# MotorShield.net
KiCad netlist of a schematic drawn in EAGLE
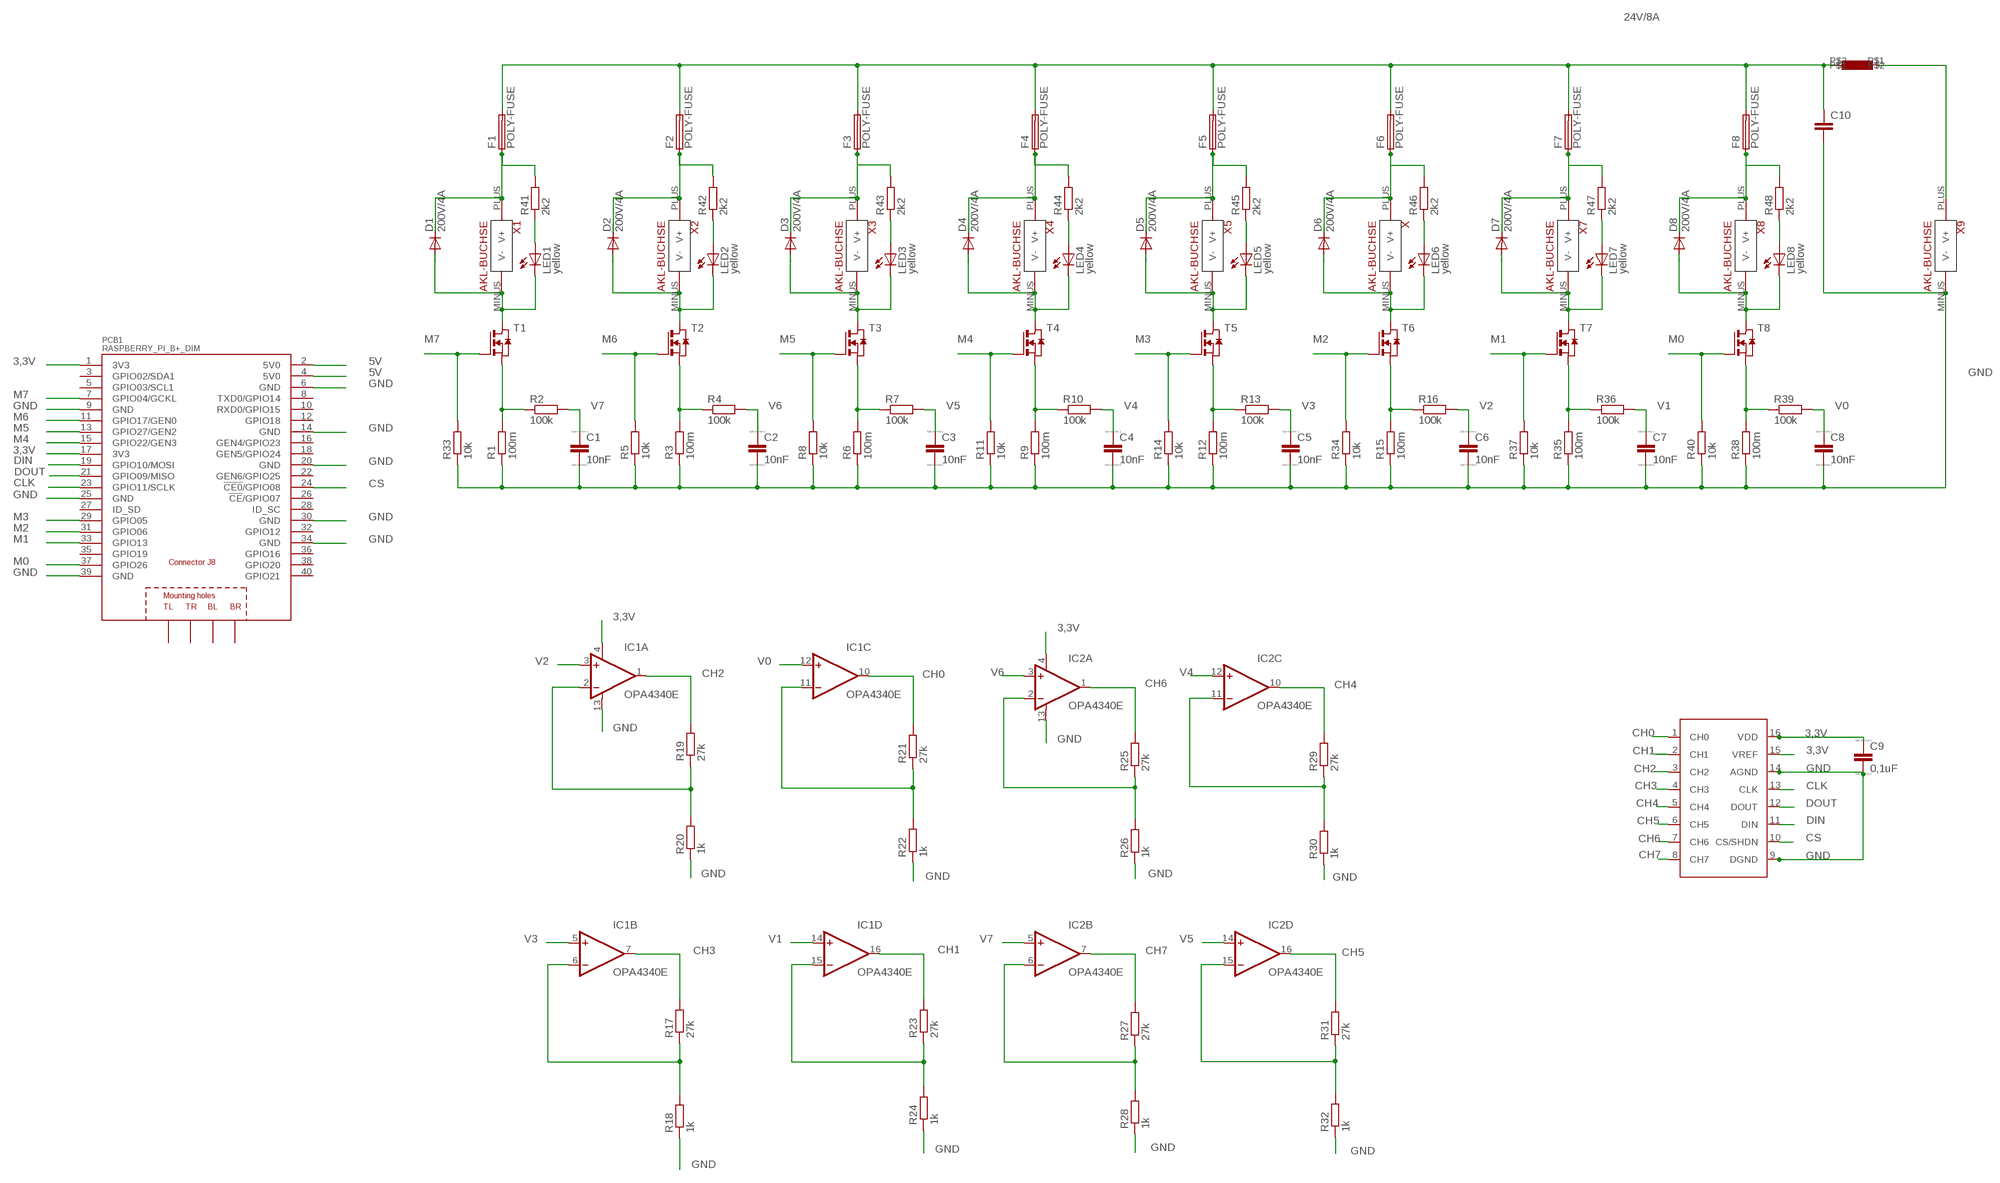
[diagram p0: schematic, sheet 1]

(export (version "E")
  (design (tool "Eeschema 10.0.6"))
  (components
    (comp (ref "C1")
      (value "10nF")
      (footprint "eagle-import:C0805")
      (libsource (lib "eagle-import") (part "C"))
    )
    (comp (ref "C2")
      (value "10nF")
      (footprint "eagle-import:C0805")
      (libsource (lib "eagle-import") (part "C"))
    )
    (comp (ref "C3")
      (value "10nF")
      (footprint "eagle-import:C0805")
      (libsource (lib "eagle-import") (part "C"))
    )
    (comp (ref "C4")
      (value "10nF")
      (footprint "eagle-import:C0805")
      (libsource (lib "eagle-import") (part "C"))
    )
    (comp (ref "C5")
      (value "10nF")
      (footprint "eagle-import:C0805")
      (libsource (lib "eagle-import") (part "C"))
    )
    (comp (ref "C6")
      (value "10nF")
      (footprint "eagle-import:C0805")
      (libsource (lib "eagle-import") (part "C"))
    )
    (comp (ref "C7")
      (value "10nF")
      (footprint "eagle-import:C0805")
      (libsource (lib "eagle-import") (part "C"))
    )
    (comp (ref "C8")
      (value "10nF")
      (footprint "eagle-import:C0805")
      (libsource (lib "eagle-import") (part "C"))
    )
    (comp (ref "C9")
      (value "0,1uF")
      (footprint "eagle-import:C0805")
      (libsource (lib "eagle-import") (part "C"))
    )
    (comp (ref "C10")
      (value "C-EUC1812")
      (footprint "eagle-import:C1812")
      (libsource (lib "eagle-import") (part "C-EUC1812"))
    )
    (comp (ref "D1")
      (value "200V/4A")
      (footprint "eagle-import:DO214AA")
      (libsource (lib "eagle-import") (part "DIODE-DO214AA"))
    )
    (comp (ref "D2")
      (value "200V/4A")
      (footprint "eagle-import:DO214AA")
      (libsource (lib "eagle-import") (part "DIODE-DO214AA"))
    )
    (comp (ref "D3")
      (value "200V/4A")
      (footprint "eagle-import:DO214AA")
      (libsource (lib "eagle-import") (part "DIODE-DO214AA"))
    )
    (comp (ref "D4")
      (value "200V/4A")
      (footprint "eagle-import:DO214AA")
      (libsource (lib "eagle-import") (part "DIODE-DO214AA"))
    )
    (comp (ref "D5")
      (value "200V/4A")
      (footprint "eagle-import:DO214AA")
      (libsource (lib "eagle-import") (part "DIODE-DO214AA"))
    )
    (comp (ref "D6")
      (value "200V/4A")
      (footprint "eagle-import:DO214AA")
      (libsource (lib "eagle-import") (part "DIODE-DO214AA"))
    )
    (comp (ref "D7")
      (value "200V/4A")
      (footprint "eagle-import:DO214AA")
      (libsource (lib "eagle-import") (part "DIODE-DO214AA"))
    )
    (comp (ref "D8")
      (value "200V/4A")
      (footprint "eagle-import:DO214AA")
      (libsource (lib "eagle-import") (part "DIODE-DO214AA"))
    )
    (comp (ref "F1")
      (value "POLY-FUSE")
      (footprint "eagle-import:1812L050")
      (libsource (lib "eagle-import") (part "POLY-FUSE"))
    )
    (comp (ref "F2")
      (value "POLY-FUSE")
      (footprint "eagle-import:1812L050")
      (libsource (lib "eagle-import") (part "POLY-FUSE"))
    )
    (comp (ref "F3")
      (value "POLY-FUSE")
      (footprint "eagle-import:1812L050")
      (libsource (lib "eagle-import") (part "POLY-FUSE"))
    )
    (comp (ref "F4")
      (value "POLY-FUSE")
      (footprint "eagle-import:1812L050")
      (libsource (lib "eagle-import") (part "POLY-FUSE"))
    )
    (comp (ref "F5")
      (value "POLY-FUSE")
      (footprint "eagle-import:1812L050")
      (libsource (lib "eagle-import") (part "POLY-FUSE"))
    )
    (comp (ref "F6")
      (value "POLY-FUSE")
      (footprint "eagle-import:1812L050")
      (libsource (lib "eagle-import") (part "POLY-FUSE"))
    )
    (comp (ref "F7")
      (value "POLY-FUSE")
      (footprint "eagle-import:1812L050")
      (libsource (lib "eagle-import") (part "POLY-FUSE"))
    )
    (comp (ref "F8")
      (value "POLY-FUSE")
      (footprint "eagle-import:1812L050")
      (libsource (lib "eagle-import") (part "POLY-FUSE"))
    )
    (comp (ref "IC1")
      (value "OPA4340E")
      (footprint "eagle-import:SSOP16BU")
      (fields (field (name "MPN") "OPA4340EA/250G4"))
      (libsource (lib "eagle-import") (part "OPA4340E"))
    )
    (comp (ref "IC2")
      (value "OPA4340E")
      (footprint "eagle-import:SSOP16BU")
      (fields (field (name "MPN") "OPA4340EA/250G4"))
      (libsource (lib "eagle-import") (part "OPA4340E"))
    )
    (comp (ref "IC3")
      (value "MCP3008SO16")
      (footprint "eagle-import:SO16")
      (libsource (lib "eagle-import") (part "MCP3008SO16"))
    )
    (comp (ref "L1")
      (value "MPI4040")
      (footprint "eagle-import:4040")
      (libsource (lib "eagle-import") (part "MPI4040"))
    )
    (comp (ref "LED1")
      (value "yellow")
      (footprint "eagle-import:CHIP-LED0603")
      (libsource (lib "eagle-import") (part "LEDCHIP-LED0603"))
    )
    (comp (ref "LED2")
      (value "yellow")
      (footprint "eagle-import:CHIP-LED0603")
      (libsource (lib "eagle-import") (part "LEDCHIP-LED0603"))
    )
    (comp (ref "LED3")
      (value "yellow")
      (footprint "eagle-import:CHIP-LED0603")
      (libsource (lib "eagle-import") (part "LEDCHIP-LED0603"))
    )
    (comp (ref "LED4")
      (value "yellow")
      (footprint "eagle-import:CHIP-LED0603")
      (libsource (lib "eagle-import") (part "LEDCHIP-LED0603"))
    )
    (comp (ref "LED5")
      (value "yellow")
      (footprint "eagle-import:CHIP-LED0603")
      (libsource (lib "eagle-import") (part "LEDCHIP-LED0603"))
    )
    (comp (ref "LED6")
      (value "yellow")
      (footprint "eagle-import:CHIP-LED0603")
      (libsource (lib "eagle-import") (part "LEDCHIP-LED0603"))
    )
    (comp (ref "LED7")
      (value "yellow")
      (footprint "eagle-import:CHIP-LED0603")
      (libsource (lib "eagle-import") (part "LEDCHIP-LED0603"))
    )
    (comp (ref "LED8")
      (value "yellow")
      (footprint "eagle-import:CHIP-LED0603")
      (libsource (lib "eagle-import") (part "LEDCHIP-LED0603"))
    )
    (comp (ref "PCB1")
      (value "RASPBERRY_PI_B+_DIM")
      (footprint "eagle-import:RASPBERRY_PI_BPLUS_DIM")
      (libsource (lib "eagle-import") (part "RASPBERRY_PI_B+_DIM"))
    )
    (comp (ref "R1")
      (value "100m")
      (footprint "eagle-import:R0805")
      (libsource (lib "eagle-import") (part "R-EU_R0805"))
    )
    (comp (ref "R2")
      (value "100k")
      (footprint "eagle-import:R0805")
      (libsource (lib "eagle-import") (part "R-EU_R0805"))
    )
    (comp (ref "R3")
      (value "100m")
      (footprint "eagle-import:R0805")
      (libsource (lib "eagle-import") (part "R-EU_R0805"))
    )
    (comp (ref "R4")
      (value "100k")
      (footprint "eagle-import:R0805")
      (libsource (lib "eagle-import") (part "R-EU_R0805"))
    )
    (comp (ref "R5")
      (value "10k")
      (footprint "eagle-import:R0805")
      (libsource (lib "eagle-import") (part "R-EU_R0805"))
    )
    (comp (ref "R6")
      (value "100m")
      (footprint "eagle-import:R0805")
      (libsource (lib "eagle-import") (part "R-EU_R0805"))
    )
    (comp (ref "R7")
      (value "100k")
      (footprint "eagle-import:R0805")
      (libsource (lib "eagle-import") (part "R-EU_R0805"))
    )
    (comp (ref "R8")
      (value "10k")
      (footprint "eagle-import:R0805")
      (libsource (lib "eagle-import") (part "R-EU_R0805"))
    )
    (comp (ref "R9")
      (value "100m")
      (footprint "eagle-import:R0805")
      (libsource (lib "eagle-import") (part "R-EU_R0805"))
    )
    (comp (ref "R10")
      (value "100k")
      (footprint "eagle-import:R0805")
      (libsource (lib "eagle-import") (part "R-EU_R0805"))
    )
    (comp (ref "R11")
      (value "10k")
      (footprint "eagle-import:R0805")
      (libsource (lib "eagle-import") (part "R-EU_R0805"))
    )
    (comp (ref "R12")
      (value "100m")
      (footprint "eagle-import:R0805")
      (libsource (lib "eagle-import") (part "R-EU_R0805"))
    )
    (comp (ref "R13")
      (value "100k")
      (footprint "eagle-import:R0805")
      (libsource (lib "eagle-import") (part "R-EU_R0805"))
    )
    (comp (ref "R14")
      (value "10k")
      (footprint "eagle-import:R0805")
      (libsource (lib "eagle-import") (part "R-EU_R0805"))
    )
    (comp (ref "R15")
      (value "100m")
      (footprint "eagle-import:R0805")
      (libsource (lib "eagle-import") (part "R-EU_R0805"))
    )
    (comp (ref "R16")
      (value "100k")
      (footprint "eagle-import:R0805")
      (libsource (lib "eagle-import") (part "R-EU_R0805"))
    )
    (comp (ref "R17")
      (value "27k")
      (footprint "eagle-import:R0805")
      (libsource (lib "eagle-import") (part "R-EU_R0805"))
    )
    (comp (ref "R18")
      (value "1k")
      (footprint "eagle-import:R0805")
      (libsource (lib "eagle-import") (part "R-EU_R0805"))
    )
    (comp (ref "R19")
      (value "27k")
      (footprint "eagle-import:R0805")
      (libsource (lib "eagle-import") (part "R-EU_R0805"))
    )
    (comp (ref "R20")
      (value "1k")
      (footprint "eagle-import:R0805")
      (libsource (lib "eagle-import") (part "R-EU_R0805"))
    )
    (comp (ref "R21")
      (value "27k")
      (footprint "eagle-import:R0805")
      (libsource (lib "eagle-import") (part "R-EU_R0805"))
    )
    (comp (ref "R22")
      (value "1k")
      (footprint "eagle-import:R0805")
      (libsource (lib "eagle-import") (part "R-EU_R0805"))
    )
    (comp (ref "R23")
      (value "27k")
      (footprint "eagle-import:R0805")
      (libsource (lib "eagle-import") (part "R-EU_R0805"))
    )
    (comp (ref "R24")
      (value "1k")
      (footprint "eagle-import:R0805")
      (libsource (lib "eagle-import") (part "R-EU_R0805"))
    )
    (comp (ref "R25")
      (value "27k")
      (footprint "eagle-import:R0805")
      (libsource (lib "eagle-import") (part "R-EU_R0805"))
    )
    (comp (ref "R26")
      (value "1k")
      (footprint "eagle-import:R0805")
      (libsource (lib "eagle-import") (part "R-EU_R0805"))
    )
    (comp (ref "R27")
      (value "27k")
      (footprint "eagle-import:R0805")
      (libsource (lib "eagle-import") (part "R-EU_R0805"))
    )
    (comp (ref "R28")
      (value "1k")
      (footprint "eagle-import:R0805")
      (libsource (lib "eagle-import") (part "R-EU_R0805"))
    )
    (comp (ref "R29")
      (value "27k")
      (footprint "eagle-import:R0805")
      (libsource (lib "eagle-import") (part "R-EU_R0805"))
    )
    (comp (ref "R30")
      (value "1k")
      (footprint "eagle-import:R0805")
      (libsource (lib "eagle-import") (part "R-EU_R0805"))
    )
    (comp (ref "R31")
      (value "27k")
      (footprint "eagle-import:R0805")
      (libsource (lib "eagle-import") (part "R-EU_R0805"))
    )
    (comp (ref "R32")
      (value "1k")
      (footprint "eagle-import:R0805")
      (libsource (lib "eagle-import") (part "R-EU_R0805"))
    )
    (comp (ref "R33")
      (value "10k")
      (footprint "eagle-import:R0805")
      (libsource (lib "eagle-import") (part "R-EU_R0805"))
    )
    (comp (ref "R34")
      (value "10k")
      (footprint "eagle-import:R0805")
      (libsource (lib "eagle-import") (part "R-EU_R0805"))
    )
    (comp (ref "R35")
      (value "100m")
      (footprint "eagle-import:R0805")
      (libsource (lib "eagle-import") (part "R-EU_R0805"))
    )
    (comp (ref "R36")
      (value "100k")
      (footprint "eagle-import:R0805")
      (libsource (lib "eagle-import") (part "R-EU_R0805"))
    )
    (comp (ref "R37")
      (value "10k")
      (footprint "eagle-import:R0805")
      (libsource (lib "eagle-import") (part "R-EU_R0805"))
    )
    (comp (ref "R38")
      (value "100m")
      (footprint "eagle-import:R0805")
      (libsource (lib "eagle-import") (part "R-EU_R0805"))
    )
    (comp (ref "R39")
      (value "100k")
      (footprint "eagle-import:R0805")
      (libsource (lib "eagle-import") (part "R-EU_R0805"))
    )
    (comp (ref "R40")
      (value "10k")
      (footprint "eagle-import:R0805")
      (libsource (lib "eagle-import") (part "R-EU_R0805"))
    )
    (comp (ref "R41")
      (value "2k2")
      (footprint "eagle-import:R0603")
      (libsource (lib "eagle-import") (part "R-EU_R0603"))
    )
    (comp (ref "R42")
      (value "2k2")
      (footprint "eagle-import:R0603")
      (libsource (lib "eagle-import") (part "R-EU_R0603"))
    )
    (comp (ref "R43")
      (value "2k2")
      (footprint "eagle-import:R0603")
      (libsource (lib "eagle-import") (part "R-EU_R0603"))
    )
    (comp (ref "R44")
      (value "2k2")
      (footprint "eagle-import:R0603")
      (libsource (lib "eagle-import") (part "R-EU_R0603"))
    )
    (comp (ref "R45")
      (value "2k2")
      (footprint "eagle-import:R0603")
      (libsource (lib "eagle-import") (part "R-EU_R0603"))
    )
    (comp (ref "R46")
      (value "2k2")
      (footprint "eagle-import:R0603")
      (libsource (lib "eagle-import") (part "R-EU_R0603"))
    )
    (comp (ref "R47")
      (value "2k2")
      (footprint "eagle-import:R0603")
      (libsource (lib "eagle-import") (part "R-EU_R0603"))
    )
    (comp (ref "R48")
      (value "2k2")
      (footprint "eagle-import:R0603")
      (libsource (lib "eagle-import") (part "R-EU_R0603"))
    )
    (comp (ref "T1")
      (value "NMOSSOT23")
      (footprint "eagle-import:SOT-23")
      (libsource (lib "eagle-import") (part "NMOSSOT23"))
    )
    (comp (ref "T2")
      (value "NMOSSOT23")
      (footprint "eagle-import:SOT-23")
      (libsource (lib "eagle-import") (part "NMOSSOT23"))
    )
    (comp (ref "T3")
      (value "NMOSSOT23")
      (footprint "eagle-import:SOT-23")
      (libsource (lib "eagle-import") (part "NMOSSOT23"))
    )
    (comp (ref "T4")
      (value "NMOSSOT23")
      (footprint "eagle-import:SOT-23")
      (libsource (lib "eagle-import") (part "NMOSSOT23"))
    )
    (comp (ref "T5")
      (value "NMOSSOT23")
      (footprint "eagle-import:SOT-23")
      (libsource (lib "eagle-import") (part "NMOSSOT23"))
    )
    (comp (ref "T6")
      (value "NMOSSOT23")
      (footprint "eagle-import:SOT-23")
      (libsource (lib "eagle-import") (part "NMOSSOT23"))
    )
    (comp (ref "T7")
      (value "NMOSSOT23")
      (footprint "eagle-import:SOT-23")
      (libsource (lib "eagle-import") (part "NMOSSOT23"))
    )
    (comp (ref "T8")
      (value "NMOSSOT23")
      (footprint "eagle-import:SOT-23")
      (libsource (lib "eagle-import") (part "NMOSSOT23"))
    )
    (comp (ref "X")
      (value "AKL-BUCHSE")
      (footprint "eagle-import:AKL-BUCHSE")
      (libsource (lib "eagle-import") (part "AKL-BUCHSE"))
    )
    (comp (ref "X1")
      (value "AKL-BUCHSE")
      (footprint "eagle-import:AKL-BUCHSE")
      (libsource (lib "eagle-import") (part "AKL-BUCHSE"))
    )
    (comp (ref "X2")
      (value "AKL-BUCHSE")
      (footprint "eagle-import:AKL-BUCHSE")
      (libsource (lib "eagle-import") (part "AKL-BUCHSE"))
    )
    (comp (ref "X3")
      (value "AKL-BUCHSE")
      (footprint "eagle-import:AKL-BUCHSE")
      (libsource (lib "eagle-import") (part "AKL-BUCHSE"))
    )
    (comp (ref "X4")
      (value "AKL-BUCHSE")
      (footprint "eagle-import:AKL-BUCHSE")
      (libsource (lib "eagle-import") (part "AKL-BUCHSE"))
    )
    (comp (ref "X5")
      (value "AKL-BUCHSE")
      (footprint "eagle-import:AKL-BUCHSE")
      (libsource (lib "eagle-import") (part "AKL-BUCHSE"))
    )
    (comp (ref "X7")
      (value "AKL-BUCHSE")
      (footprint "eagle-import:AKL-BUCHSE")
      (libsource (lib "eagle-import") (part "AKL-BUCHSE"))
    )
    (comp (ref "X8")
      (value "AKL-BUCHSE")
      (footprint "eagle-import:AKL-BUCHSE")
      (libsource (lib "eagle-import") (part "AKL-BUCHSE"))
    )
    (comp (ref "X9")
      (value "AKL-BUCHSE")
      (footprint "eagle-import:AKL-BUCHSE")
      (libsource (lib "eagle-import") (part "AKL-BUCHSE"))
    )
  )
  (nets
    (net (code "1") (name "/3,3V") (class "Default")
      (node (ref "C9") (pin "1") (pinfunction "1_1") (pintype "passive"))
      (node (ref "IC1") (pin "4") (pinfunction "V+_4") (pintype "power_in"))
      (node (ref "IC2") (pin "4") (pinfunction "V+_4") (pintype "power_in"))
      (node (ref "IC3") (pin "15") (pinfunction "VREF_15") (pintype "bidirectional"))
      (node (ref "IC3") (pin "16") (pinfunction "VDD_16") (pintype "bidirectional"))
      (node (ref "PCB1") (pin "1") (pinfunction "3V3_1") (pintype "power_in"))
      (node (ref "PCB1") (pin "17") (pinfunction "3V3_17") (pintype "power_in"))
    )
    (net (code "2") (name "/5V") (class "Default")
      (node (ref "PCB1") (pin "2") (pinfunction "5V0_2") (pintype "power_in"))
      (node (ref "PCB1") (pin "4") (pinfunction "5V0_4") (pintype "power_in"))
    )
    (net (code "3") (name "/24V{slash}8A") (class "Default")
      (node (ref "C10") (pin "1") (pinfunction "1_1") (pintype "passive"))
      (node (ref "F1") (pin "P$2") (pinfunction "2_P$2") (pintype "passive"))
      (node (ref "F2") (pin "P$2") (pinfunction "2_P$2") (pintype "passive"))
      (node (ref "F3") (pin "P$2") (pinfunction "2_P$2") (pintype "passive"))
      (node (ref "F4") (pin "P$2") (pinfunction "2_P$2") (pintype "passive"))
      (node (ref "F5") (pin "P$2") (pinfunction "2_P$2") (pintype "passive"))
      (node (ref "F6") (pin "P$2") (pinfunction "2_P$2") (pintype "passive"))
      (node (ref "F7") (pin "P$2") (pinfunction "2_P$2") (pintype "passive"))
      (node (ref "F8") (pin "P$2") (pinfunction "2_P$2") (pintype "passive"))
      (node (ref "L1") (pin "P$2") (pinfunction "P$2_P$2") (pintype "bidirectional"))
    )
    (net (code "4") (name "/CH0") (class "Default")
      (node (ref "IC1") (pin "10") (pinfunction "OUT_10") (pintype "output"))
      (node (ref "IC3") (pin "1") (pinfunction "CH0_1") (pintype "bidirectional"))
      (node (ref "R21") (pin "2") (pinfunction "2_2") (pintype "passive"))
    )
    (net (code "5") (name "/CH1") (class "Default")
      (node (ref "IC1") (pin "16") (pinfunction "OUT_16") (pintype "output"))
      (node (ref "IC3") (pin "2") (pinfunction "CH1_2") (pintype "bidirectional"))
      (node (ref "R23") (pin "2") (pinfunction "2_2") (pintype "passive"))
    )
    (net (code "6") (name "/CH2") (class "Default")
      (node (ref "IC1") (pin "1") (pinfunction "OUT_1") (pintype "output"))
      (node (ref "IC3") (pin "3") (pinfunction "CH2_3") (pintype "bidirectional"))
      (node (ref "R19") (pin "2") (pinfunction "2_2") (pintype "passive"))
    )
    (net (code "7") (name "/CH3") (class "Default")
      (node (ref "IC1") (pin "7") (pinfunction "OUT_7") (pintype "output"))
      (node (ref "IC3") (pin "4") (pinfunction "CH3_4") (pintype "bidirectional"))
      (node (ref "R17") (pin "2") (pinfunction "2_2") (pintype "passive"))
    )
    (net (code "8") (name "/CH4") (class "Default")
      (node (ref "IC2") (pin "10") (pinfunction "OUT_10") (pintype "output"))
      (node (ref "IC3") (pin "5") (pinfunction "CH4_5") (pintype "bidirectional"))
      (node (ref "R29") (pin "2") (pinfunction "2_2") (pintype "passive"))
    )
    (net (code "9") (name "/CH5") (class "Default")
      (node (ref "IC2") (pin "16") (pinfunction "OUT_16") (pintype "output"))
      (node (ref "IC3") (pin "6") (pinfunction "CH5_6") (pintype "bidirectional"))
      (node (ref "R31") (pin "2") (pinfunction "2_2") (pintype "passive"))
    )
    (net (code "10") (name "/CH6") (class "Default")
      (node (ref "IC2") (pin "1") (pinfunction "OUT_1") (pintype "output"))
      (node (ref "IC3") (pin "7") (pinfunction "CH6_7") (pintype "bidirectional"))
      (node (ref "R25") (pin "2") (pinfunction "2_2") (pintype "passive"))
    )
    (net (code "11") (name "/CH7") (class "Default")
      (node (ref "IC2") (pin "7") (pinfunction "OUT_7") (pintype "output"))
      (node (ref "IC3") (pin "8") (pinfunction "CH7_8") (pintype "bidirectional"))
      (node (ref "R27") (pin "2") (pinfunction "2_2") (pintype "passive"))
    )
    (net (code "12") (name "/CLK") (class "Default")
      (node (ref "IC3") (pin "13") (pinfunction "CLK_13") (pintype "bidirectional"))
      (node (ref "PCB1") (pin "23") (pinfunction "GPIO11/SCLK_23") (pintype "bidirectional"))
    )
    (net (code "13") (name "/CS") (class "Default")
      (node (ref "IC3") (pin "10") (pinfunction "CS/SHDN_10") (pintype "bidirectional"))
      (node (ref "PCB1") (pin "24") (pinfunction "~{CE0}/GPIO08_24") (pintype "bidirectional"))
    )
    (net (code "14") (name "/DIN") (class "Default")
      (node (ref "IC3") (pin "11") (pinfunction "DIN_11") (pintype "bidirectional"))
      (node (ref "PCB1") (pin "19") (pinfunction "GPIO10/MOSI_19") (pintype "bidirectional"))
    )
    (net (code "15") (name "/DOUT") (class "Default")
      (node (ref "IC3") (pin "12") (pinfunction "DOUT_12") (pintype "bidirectional"))
      (node (ref "PCB1") (pin "21") (pinfunction "GPIO09/MISO_21") (pintype "bidirectional"))
    )
    (net (code "16") (name "/GND") (class "Default")
      (node (ref "C1") (pin "2") (pinfunction "2_2") (pintype "passive"))
      (node (ref "C10") (pin "2") (pinfunction "2_2") (pintype "passive"))
      (node (ref "C2") (pin "2") (pinfunction "2_2") (pintype "passive"))
      (node (ref "C3") (pin "2") (pinfunction "2_2") (pintype "passive"))
      (node (ref "C4") (pin "2") (pinfunction "2_2") (pintype "passive"))
      (node (ref "C5") (pin "2") (pinfunction "2_2") (pintype "passive"))
      (node (ref "C6") (pin "2") (pinfunction "2_2") (pintype "passive"))
      (node (ref "C7") (pin "2") (pinfunction "2_2") (pintype "passive"))
      (node (ref "C8") (pin "2") (pinfunction "2_2") (pintype "passive"))
      (node (ref "C9") (pin "2") (pinfunction "2_2") (pintype "passive"))
      (node (ref "IC1") (pin "13") (pinfunction "V-_13") (pintype "power_in"))
      (node (ref "IC2") (pin "13") (pinfunction "V-_13") (pintype "power_in"))
      (node (ref "IC3") (pin "14") (pinfunction "AGND_14") (pintype "bidirectional"))
      (node (ref "IC3") (pin "9") (pinfunction "DGND_9") (pintype "bidirectional"))
      (node (ref "PCB1") (pin "14") (pinfunction "GND_14") (pintype "power_in"))
      (node (ref "PCB1") (pin "20") (pinfunction "GND_20") (pintype "power_in"))
      (node (ref "PCB1") (pin "25") (pinfunction "GND_25") (pintype "power_in"))
      (node (ref "PCB1") (pin "30") (pinfunction "GND_30") (pintype "power_in"))
      (node (ref "PCB1") (pin "34") (pinfunction "GND_34") (pintype "power_in"))
      (node (ref "PCB1") (pin "39") (pinfunction "GND_39") (pintype "power_in"))
      (node (ref "PCB1") (pin "6") (pinfunction "GND_6") (pintype "power_in"))
      (node (ref "PCB1") (pin "9") (pinfunction "GND_9") (pintype "power_in"))
      (node (ref "R1") (pin "1") (pinfunction "1_1") (pintype "passive"))
      (node (ref "R11") (pin "1") (pinfunction "1_1") (pintype "passive"))
      (node (ref "R12") (pin "1") (pinfunction "1_1") (pintype "passive"))
      (node (ref "R14") (pin "1") (pinfunction "1_1") (pintype "passive"))
      (node (ref "R15") (pin "1") (pinfunction "1_1") (pintype "passive"))
      (node (ref "R18") (pin "1") (pinfunction "1_1") (pintype "passive"))
      (node (ref "R20") (pin "1") (pinfunction "1_1") (pintype "passive"))
      (node (ref "R22") (pin "1") (pinfunction "1_1") (pintype "passive"))
      (node (ref "R24") (pin "1") (pinfunction "1_1") (pintype "passive"))
      (node (ref "R26") (pin "1") (pinfunction "1_1") (pintype "passive"))
      (node (ref "R28") (pin "1") (pinfunction "1_1") (pintype "passive"))
      (node (ref "R3") (pin "1") (pinfunction "1_1") (pintype "passive"))
      (node (ref "R30") (pin "1") (pinfunction "1_1") (pintype "passive"))
      (node (ref "R32") (pin "1") (pinfunction "1_1") (pintype "passive"))
      (node (ref "R33") (pin "1") (pinfunction "1_1") (pintype "passive"))
      (node (ref "R34") (pin "1") (pinfunction "1_1") (pintype "passive"))
      (node (ref "R35") (pin "1") (pinfunction "1_1") (pintype "passive"))
      (node (ref "R37") (pin "1") (pinfunction "1_1") (pintype "passive"))
      (node (ref "R38") (pin "1") (pinfunction "1_1") (pintype "passive"))
      (node (ref "R40") (pin "1") (pinfunction "1_1") (pintype "passive"))
      (node (ref "R5") (pin "1") (pinfunction "1_1") (pintype "passive"))
      (node (ref "R6") (pin "1") (pinfunction "1_1") (pintype "passive"))
      (node (ref "R8") (pin "1") (pinfunction "1_1") (pintype "passive"))
      (node (ref "R9") (pin "1") (pinfunction "1_1") (pintype "passive"))
      (node (ref "X9") (pin "MINUS") (pinfunction "V-_MINUS") (pintype "bidirectional"))
    )
    (net (code "17") (name "/M0") (class "Default")
      (node (ref "PCB1") (pin "37") (pinfunction "GPIO26_37") (pintype "bidirectional"))
      (node (ref "R40") (pin "2") (pinfunction "2_2") (pintype "passive"))
      (node (ref "T8") (pin "3") (pinfunction "G_3") (pintype "passive"))
    )
    (net (code "18") (name "/M1") (class "Default")
      (node (ref "PCB1") (pin "33") (pinfunction "GPIO13_33") (pintype "bidirectional"))
      (node (ref "R37") (pin "2") (pinfunction "2_2") (pintype "passive"))
      (node (ref "T7") (pin "3") (pinfunction "G_3") (pintype "passive"))
    )
    (net (code "19") (name "/M2") (class "Default")
      (node (ref "PCB1") (pin "31") (pinfunction "GPIO06_31") (pintype "bidirectional"))
      (node (ref "R34") (pin "2") (pinfunction "2_2") (pintype "passive"))
      (node (ref "T6") (pin "3") (pinfunction "G_3") (pintype "passive"))
    )
    (net (code "20") (name "/M3") (class "Default")
      (node (ref "PCB1") (pin "29") (pinfunction "GPIO05_29") (pintype "bidirectional"))
      (node (ref "R14") (pin "2") (pinfunction "2_2") (pintype "passive"))
      (node (ref "T5") (pin "3") (pinfunction "G_3") (pintype "passive"))
    )
    (net (code "21") (name "/M4") (class "Default")
      (node (ref "PCB1") (pin "15") (pinfunction "GPIO22/GEN3_15") (pintype "bidirectional"))
      (node (ref "R11") (pin "2") (pinfunction "2_2") (pintype "passive"))
      (node (ref "T4") (pin "3") (pinfunction "G_3") (pintype "passive"))
    )
    (net (code "22") (name "/M5") (class "Default")
      (node (ref "PCB1") (pin "13") (pinfunction "GPIO27/GEN2_13") (pintype "bidirectional"))
      (node (ref "R8") (pin "2") (pinfunction "2_2") (pintype "passive"))
      (node (ref "T3") (pin "3") (pinfunction "G_3") (pintype "passive"))
    )
    (net (code "23") (name "/M6") (class "Default")
      (node (ref "PCB1") (pin "11") (pinfunction "GPIO17/GEN0_11") (pintype "bidirectional"))
      (node (ref "R5") (pin "2") (pinfunction "2_2") (pintype "passive"))
      (node (ref "T2") (pin "3") (pinfunction "G_3") (pintype "passive"))
    )
    (net (code "24") (name "/M7") (class "Default")
      (node (ref "PCB1") (pin "7") (pinfunction "GPIO04/GCKL_7") (pintype "bidirectional"))
      (node (ref "R33") (pin "2") (pinfunction "2_2") (pintype "passive"))
      (node (ref "T1") (pin "3") (pinfunction "G_3") (pintype "passive"))
    )
    (net (code "25") (name "/V0") (class "Default")
      (node (ref "C8") (pin "1") (pinfunction "1_1") (pintype "passive"))
      (node (ref "IC1") (pin "12") (pinfunction "+IN_12") (pintype "input"))
      (node (ref "R39") (pin "2") (pinfunction "2_2") (pintype "passive"))
    )
    (net (code "26") (name "/V1") (class "Default")
      (node (ref "C7") (pin "1") (pinfunction "1_1") (pintype "passive"))
      (node (ref "IC1") (pin "14") (pinfunction "+IN_14") (pintype "input"))
      (node (ref "R36") (pin "2") (pinfunction "2_2") (pintype "passive"))
    )
    (net (code "27") (name "/V2") (class "Default")
      (node (ref "C6") (pin "1") (pinfunction "1_1") (pintype "passive"))
      (node (ref "IC1") (pin "3") (pinfunction "+IN_3") (pintype "input"))
      (node (ref "R16") (pin "2") (pinfunction "2_2") (pintype "passive"))
    )
    (net (code "28") (name "/V3") (class "Default")
      (node (ref "C5") (pin "1") (pinfunction "1_1") (pintype "passive"))
      (node (ref "IC1") (pin "5") (pinfunction "+IN_5") (pintype "input"))
      (node (ref "R13") (pin "2") (pinfunction "2_2") (pintype "passive"))
    )
    (net (code "29") (name "/V4") (class "Default")
      (node (ref "C4") (pin "1") (pinfunction "1_1") (pintype "passive"))
      (node (ref "IC2") (pin "12") (pinfunction "+IN_12") (pintype "input"))
      (node (ref "R10") (pin "2") (pinfunction "2_2") (pintype "passive"))
    )
    (net (code "30") (name "/V5") (class "Default")
      (node (ref "C3") (pin "1") (pinfunction "1_1") (pintype "passive"))
      (node (ref "IC2") (pin "14") (pinfunction "+IN_14") (pintype "input"))
      (node (ref "R7") (pin "2") (pinfunction "2_2") (pintype "passive"))
    )
    (net (code "31") (name "/V6") (class "Default")
      (node (ref "C2") (pin "1") (pinfunction "1_1") (pintype "passive"))
      (node (ref "IC2") (pin "3") (pinfunction "+IN_3") (pintype "input"))
      (node (ref "R4") (pin "2") (pinfunction "2_2") (pintype "passive"))
    )
    (net (code "32") (name "/V7") (class "Default")
      (node (ref "C1") (pin "1") (pinfunction "1_1") (pintype "passive"))
      (node (ref "IC2") (pin "5") (pinfunction "+IN_5") (pintype "input"))
      (node (ref "R2") (pin "2") (pinfunction "2_2") (pintype "passive"))
    )
    (net (code "33") (name "Net-(F1-1)") (class "Default")
      (node (ref "D1") (pin "C") (pinfunction "C_C") (pintype "passive"))
      (node (ref "F1") (pin "P$1") (pinfunction "1_P$1") (pintype "passive"))
      (node (ref "R41") (pin "2") (pinfunction "2_2") (pintype "passive"))
      (node (ref "X1") (pin "PLUS") (pinfunction "V+_PLUS") (pintype "bidirectional"))
    )
    (net (code "34") (name "Net-(F2-1)") (class "Default")
      (node (ref "D2") (pin "C") (pinfunction "C_C") (pintype "passive"))
      (node (ref "F2") (pin "P$1") (pinfunction "1_P$1") (pintype "passive"))
      (node (ref "R42") (pin "2") (pinfunction "2_2") (pintype "passive"))
      (node (ref "X2") (pin "PLUS") (pinfunction "V+_PLUS") (pintype "bidirectional"))
    )
    (net (code "35") (name "Net-(F3-1)") (class "Default")
      (node (ref "D3") (pin "C") (pinfunction "C_C") (pintype "passive"))
      (node (ref "F3") (pin "P$1") (pinfunction "1_P$1") (pintype "passive"))
      (node (ref "R43") (pin "2") (pinfunction "2_2") (pintype "passive"))
      (node (ref "X3") (pin "PLUS") (pinfunction "V+_PLUS") (pintype "bidirectional"))
    )
    (net (code "36") (name "Net-(F4-1)") (class "Default")
      (node (ref "D4") (pin "C") (pinfunction "C_C") (pintype "passive"))
      (node (ref "F4") (pin "P$1") (pinfunction "1_P$1") (pintype "passive"))
      (node (ref "R44") (pin "2") (pinfunction "2_2") (pintype "passive"))
      (node (ref "X4") (pin "PLUS") (pinfunction "V+_PLUS") (pintype "bidirectional"))
    )
    (net (code "37") (name "Net-(F5-1)") (class "Default")
      (node (ref "D5") (pin "C") (pinfunction "C_C") (pintype "passive"))
      (node (ref "F5") (pin "P$1") (pinfunction "1_P$1") (pintype "passive"))
      (node (ref "R45") (pin "2") (pinfunction "2_2") (pintype "passive"))
      (node (ref "X5") (pin "PLUS") (pinfunction "V+_PLUS") (pintype "bidirectional"))
    )
    (net (code "38") (name "Net-(F6-1)") (class "Default")
      (node (ref "D6") (pin "C") (pinfunction "C_C") (pintype "passive"))
      (node (ref "F6") (pin "P$1") (pinfunction "1_P$1") (pintype "passive"))
      (node (ref "R46") (pin "2") (pinfunction "2_2") (pintype "passive"))
      (node (ref "X") (pin "PLUS") (pinfunction "V+_PLUS") (pintype "bidirectional"))
    )
    (net (code "39") (name "Net-(F7-1)") (class "Default")
      (node (ref "D7") (pin "C") (pinfunction "C_C") (pintype "passive"))
      (node (ref "F7") (pin "P$1") (pinfunction "1_P$1") (pintype "passive"))
      (node (ref "R47") (pin "2") (pinfunction "2_2") (pintype "passive"))
      (node (ref "X7") (pin "PLUS") (pinfunction "V+_PLUS") (pintype "bidirectional"))
    )
    (net (code "40") (name "Net-(F8-1)") (class "Default")
      (node (ref "D8") (pin "C") (pinfunction "C_C") (pintype "passive"))
      (node (ref "F8") (pin "P$1") (pinfunction "1_P$1") (pintype "passive"))
      (node (ref "R48") (pin "2") (pinfunction "2_2") (pintype "passive"))
      (node (ref "X8") (pin "PLUS") (pinfunction "V+_PLUS") (pintype "bidirectional"))
    )
    (net (code "41") (name "Net-(IC1A--IN)") (class "Default")
      (node (ref "IC1") (pin "2") (pinfunction "-IN_2") (pintype "input"))
      (node (ref "R19") (pin "1") (pinfunction "1_1") (pintype "passive"))
      (node (ref "R20") (pin "2") (pinfunction "2_2") (pintype "passive"))
    )
    (net (code "42") (name "Net-(IC1B--IN)") (class "Default")
      (node (ref "IC1") (pin "6") (pinfunction "-IN_6") (pintype "input"))
      (node (ref "R17") (pin "1") (pinfunction "1_1") (pintype "passive"))
      (node (ref "R18") (pin "2") (pinfunction "2_2") (pintype "passive"))
    )
    (net (code "43") (name "Net-(IC1C--IN)") (class "Default")
      (node (ref "IC1") (pin "11") (pinfunction "-IN_11") (pintype "input"))
      (node (ref "R21") (pin "1") (pinfunction "1_1") (pintype "passive"))
      (node (ref "R22") (pin "2") (pinfunction "2_2") (pintype "passive"))
    )
    (net (code "44") (name "Net-(IC1D--IN)") (class "Default")
      (node (ref "IC1") (pin "15") (pinfunction "-IN_15") (pintype "input"))
      (node (ref "R23") (pin "1") (pinfunction "1_1") (pintype "passive"))
      (node (ref "R24") (pin "2") (pinfunction "2_2") (pintype "passive"))
    )
    (net (code "45") (name "Net-(IC2A--IN)") (class "Default")
      (node (ref "IC2") (pin "2") (pinfunction "-IN_2") (pintype "input"))
      (node (ref "R25") (pin "1") (pinfunction "1_1") (pintype "passive"))
      (node (ref "R26") (pin "2") (pinfunction "2_2") (pintype "passive"))
    )
    (net (code "46") (name "Net-(IC2B--IN)") (class "Default")
      (node (ref "IC2") (pin "6") (pinfunction "-IN_6") (pintype "input"))
      (node (ref "R27") (pin "1") (pinfunction "1_1") (pintype "passive"))
      (node (ref "R28") (pin "2") (pinfunction "2_2") (pintype "passive"))
    )
    (net (code "47") (name "Net-(IC2C--IN)") (class "Default")
      (node (ref "IC2") (pin "11") (pinfunction "-IN_11") (pintype "input"))
      (node (ref "R29") (pin "1") (pinfunction "1_1") (pintype "passive"))
      (node (ref "R30") (pin "2") (pinfunction "2_2") (pintype "passive"))
    )
    (net (code "48") (name "Net-(IC2D--IN)") (class "Default")
      (node (ref "IC2") (pin "15") (pinfunction "-IN_15") (pintype "input"))
      (node (ref "R31") (pin "1") (pinfunction "1_1") (pintype "passive"))
      (node (ref "R32") (pin "2") (pinfunction "2_2") (pintype "passive"))
    )
    (net (code "49") (name "Net-(LED1-PadA)") (class "Default")
      (node (ref "LED1") (pin "A") (pinfunction "A_A") (pintype "passive"))
      (node (ref "R41") (pin "1") (pinfunction "1_1") (pintype "passive"))
    )
    (net (code "50") (name "Net-(LED2-PadA)") (class "Default")
      (node (ref "LED2") (pin "A") (pinfunction "A_A") (pintype "passive"))
      (node (ref "R42") (pin "1") (pinfunction "1_1") (pintype "passive"))
    )
    (net (code "51") (name "Net-(LED3-PadA)") (class "Default")
      (node (ref "LED3") (pin "A") (pinfunction "A_A") (pintype "passive"))
      (node (ref "R43") (pin "1") (pinfunction "1_1") (pintype "passive"))
    )
    (net (code "52") (name "Net-(LED4-PadA)") (class "Default")
      (node (ref "LED4") (pin "A") (pinfunction "A_A") (pintype "passive"))
      (node (ref "R44") (pin "1") (pinfunction "1_1") (pintype "passive"))
    )
    (net (code "53") (name "Net-(LED5-PadA)") (class "Default")
      (node (ref "LED5") (pin "A") (pinfunction "A_A") (pintype "passive"))
      (node (ref "R45") (pin "1") (pinfunction "1_1") (pintype "passive"))
    )
    (net (code "54") (name "Net-(LED6-PadA)") (class "Default")
      (node (ref "LED6") (pin "A") (pinfunction "A_A") (pintype "passive"))
      (node (ref "R46") (pin "1") (pinfunction "1_1") (pintype "passive"))
    )
    (net (code "55") (name "Net-(LED7-PadA)") (class "Default")
      (node (ref "LED7") (pin "A") (pinfunction "A_A") (pintype "passive"))
      (node (ref "R47") (pin "1") (pinfunction "1_1") (pintype "passive"))
    )
    (net (code "56") (name "Net-(LED8-PadA)") (class "Default")
      (node (ref "LED8") (pin "A") (pinfunction "A_A") (pintype "passive"))
      (node (ref "R48") (pin "1") (pinfunction "1_1") (pintype "passive"))
    )
    (net (code "57") (name "Net-(T1-D)") (class "Default")
      (node (ref "D1") (pin "A") (pinfunction "A_A") (pintype "passive"))
      (node (ref "LED1") (pin "C") (pinfunction "C_C") (pintype "passive"))
      (node (ref "T1") (pin "1") (pinfunction "D_1") (pintype "passive"))
      (node (ref "X1") (pin "MINUS") (pinfunction "V-_MINUS") (pintype "bidirectional"))
    )
    (net (code "58") (name "Net-(T1-S)") (class "Default")
      (node (ref "R1") (pin "2") (pinfunction "2_2") (pintype "passive"))
      (node (ref "R2") (pin "1") (pinfunction "1_1") (pintype "passive"))
      (node (ref "T1") (pin "2") (pinfunction "S_2") (pintype "passive"))
    )
    (net (code "59") (name "Net-(T2-D)") (class "Default")
      (node (ref "D2") (pin "A") (pinfunction "A_A") (pintype "passive"))
      (node (ref "LED2") (pin "C") (pinfunction "C_C") (pintype "passive"))
      (node (ref "T2") (pin "1") (pinfunction "D_1") (pintype "passive"))
      (node (ref "X2") (pin "MINUS") (pinfunction "V-_MINUS") (pintype "bidirectional"))
    )
    (net (code "60") (name "Net-(T2-S)") (class "Default")
      (node (ref "R3") (pin "2") (pinfunction "2_2") (pintype "passive"))
      (node (ref "R4") (pin "1") (pinfunction "1_1") (pintype "passive"))
      (node (ref "T2") (pin "2") (pinfunction "S_2") (pintype "passive"))
    )
    (net (code "61") (name "Net-(T3-D)") (class "Default")
      (node (ref "D3") (pin "A") (pinfunction "A_A") (pintype "passive"))
      (node (ref "LED3") (pin "C") (pinfunction "C_C") (pintype "passive"))
      (node (ref "T3") (pin "1") (pinfunction "D_1") (pintype "passive"))
      (node (ref "X3") (pin "MINUS") (pinfunction "V-_MINUS") (pintype "bidirectional"))
    )
    (net (code "62") (name "Net-(T3-S)") (class "Default")
      (node (ref "R6") (pin "2") (pinfunction "2_2") (pintype "passive"))
      (node (ref "R7") (pin "1") (pinfunction "1_1") (pintype "passive"))
      (node (ref "T3") (pin "2") (pinfunction "S_2") (pintype "passive"))
    )
    (net (code "63") (name "Net-(T4-D)") (class "Default")
      (node (ref "D4") (pin "A") (pinfunction "A_A") (pintype "passive"))
      (node (ref "LED4") (pin "C") (pinfunction "C_C") (pintype "passive"))
      (node (ref "T4") (pin "1") (pinfunction "D_1") (pintype "passive"))
      (node (ref "X4") (pin "MINUS") (pinfunction "V-_MINUS") (pintype "bidirectional"))
    )
    (net (code "64") (name "Net-(T4-S)") (class "Default")
      (node (ref "R10") (pin "1") (pinfunction "1_1") (pintype "passive"))
      (node (ref "R9") (pin "2") (pinfunction "2_2") (pintype "passive"))
      (node (ref "T4") (pin "2") (pinfunction "S_2") (pintype "passive"))
    )
    (net (code "65") (name "Net-(T5-D)") (class "Default")
      (node (ref "D5") (pin "A") (pinfunction "A_A") (pintype "passive"))
      (node (ref "LED5") (pin "C") (pinfunction "C_C") (pintype "passive"))
      (node (ref "T5") (pin "1") (pinfunction "D_1") (pintype "passive"))
      (node (ref "X5") (pin "MINUS") (pinfunction "V-_MINUS") (pintype "bidirectional"))
    )
    (net (code "66") (name "Net-(T5-S)") (class "Default")
      (node (ref "R12") (pin "2") (pinfunction "2_2") (pintype "passive"))
      (node (ref "R13") (pin "1") (pinfunction "1_1") (pintype "passive"))
      (node (ref "T5") (pin "2") (pinfunction "S_2") (pintype "passive"))
    )
    (net (code "67") (name "Net-(T6-D)") (class "Default")
      (node (ref "D6") (pin "A") (pinfunction "A_A") (pintype "passive"))
      (node (ref "LED6") (pin "C") (pinfunction "C_C") (pintype "passive"))
      (node (ref "T6") (pin "1") (pinfunction "D_1") (pintype "passive"))
      (node (ref "X") (pin "MINUS") (pinfunction "V-_MINUS") (pintype "bidirectional"))
    )
    (net (code "68") (name "Net-(T6-S)") (class "Default")
      (node (ref "R15") (pin "2") (pinfunction "2_2") (pintype "passive"))
      (node (ref "R16") (pin "1") (pinfunction "1_1") (pintype "passive"))
      (node (ref "T6") (pin "2") (pinfunction "S_2") (pintype "passive"))
    )
    (net (code "69") (name "Net-(T7-D)") (class "Default")
      (node (ref "D7") (pin "A") (pinfunction "A_A") (pintype "passive"))
      (node (ref "LED7") (pin "C") (pinfunction "C_C") (pintype "passive"))
      (node (ref "T7") (pin "1") (pinfunction "D_1") (pintype "passive"))
      (node (ref "X7") (pin "MINUS") (pinfunction "V-_MINUS") (pintype "bidirectional"))
    )
    (net (code "70") (name "Net-(T7-S)") (class "Default")
      (node (ref "R35") (pin "2") (pinfunction "2_2") (pintype "passive"))
      (node (ref "R36") (pin "1") (pinfunction "1_1") (pintype "passive"))
      (node (ref "T7") (pin "2") (pinfunction "S_2") (pintype "passive"))
    )
    (net (code "71") (name "Net-(T8-D)") (class "Default")
      (node (ref "D8") (pin "A") (pinfunction "A_A") (pintype "passive"))
      (node (ref "LED8") (pin "C") (pinfunction "C_C") (pintype "passive"))
      (node (ref "T8") (pin "1") (pinfunction "D_1") (pintype "passive"))
      (node (ref "X8") (pin "MINUS") (pinfunction "V-_MINUS") (pintype "bidirectional"))
    )
    (net (code "72") (name "Net-(T8-S)") (class "Default")
      (node (ref "R38") (pin "2") (pinfunction "2_2") (pintype "passive"))
      (node (ref "R39") (pin "1") (pinfunction "1_1") (pintype "passive"))
      (node (ref "T8") (pin "2") (pinfunction "S_2") (pintype "passive"))
    )
    (net (code "73") (name "Net-(X9-V+)") (class "Default")
      (node (ref "L1") (pin "P$1") (pinfunction "P$1_P$1") (pintype "bidirectional"))
      (node (ref "X9") (pin "PLUS") (pinfunction "V+_PLUS") (pintype "bidirectional"))
    )
    (net (code "74") (name "unconnected-(PCB1-BL-PadPE_BL)") (class "Default")
      (node (ref "PCB1") (pin "PE_BL") (pinfunction "BL_PE_BL") (pintype "bidirectional"))
    )
    (net (code "75") (name "unconnected-(PCB1-BR-PadPE_BR)") (class "Default")
      (node (ref "PCB1") (pin "PE_BR") (pinfunction "BR_PE_BR") (pintype "bidirectional"))
    )
    (net (code "76") (name "unconnected-(PCB1-GEN4{slash}GPIO23-Pad16)") (class "Default")
      (node (ref "PCB1") (pin "16") (pinfunction "GEN4/GPIO23_16") (pintype "bidirectional"))
    )
    (net (code "77") (name "unconnected-(PCB1-GEN5{slash}GPIO24-Pad18)") (class "Default")
      (node (ref "PCB1") (pin "18") (pinfunction "GEN5/GPIO24_18") (pintype "bidirectional"))
    )
    (net (code "78") (name "unconnected-(PCB1-GEN6{slash}GPIO25-Pad22)") (class "Default")
      (node (ref "PCB1") (pin "22") (pinfunction "GEN6/GPIO25_22") (pintype "bidirectional"))
    )
    (net (code "79") (name "unconnected-(PCB1-GPIO02{slash}SDA1-Pad3)") (class "Default")
      (node (ref "PCB1") (pin "3") (pinfunction "GPIO02/SDA1_3") (pintype "bidirectional"))
    )
    (net (code "80") (name "unconnected-(PCB1-GPIO03{slash}SCL1-Pad5)") (class "Default")
      (node (ref "PCB1") (pin "5") (pinfunction "GPIO03/SCL1_5") (pintype "bidirectional"))
    )
    (net (code "81") (name "unconnected-(PCB1-GPIO12-Pad32)") (class "Default")
      (node (ref "PCB1") (pin "32") (pinfunction "GPIO12_32") (pintype "bidirectional"))
    )
    (net (code "82") (name "unconnected-(PCB1-GPIO16-Pad36)") (class "Default")
      (node (ref "PCB1") (pin "36") (pinfunction "GPIO16_36") (pintype "bidirectional"))
    )
    (net (code "83") (name "unconnected-(PCB1-GPIO18-Pad12)") (class "Default")
      (node (ref "PCB1") (pin "12") (pinfunction "GPIO18_12") (pintype "bidirectional"))
    )
    (net (code "84") (name "unconnected-(PCB1-GPIO19-Pad35)") (class "Default")
      (node (ref "PCB1") (pin "35") (pinfunction "GPIO19_35") (pintype "bidirectional"))
    )
    (net (code "85") (name "unconnected-(PCB1-GPIO20-Pad38)") (class "Default")
      (node (ref "PCB1") (pin "38") (pinfunction "GPIO20_38") (pintype "bidirectional"))
    )
    (net (code "86") (name "unconnected-(PCB1-GPIO21-Pad40)") (class "Default")
      (node (ref "PCB1") (pin "40") (pinfunction "GPIO21_40") (pintype "bidirectional"))
    )
    (net (code "87") (name "unconnected-(PCB1-ID_SC-Pad28)") (class "Default")
      (node (ref "PCB1") (pin "28") (pinfunction "ID_SC_28") (pintype "bidirectional"))
    )
    (net (code "88") (name "unconnected-(PCB1-ID_SD-Pad27)") (class "Default")
      (node (ref "PCB1") (pin "27") (pinfunction "ID_SD_27") (pintype "bidirectional"))
    )
    (net (code "89") (name "unconnected-(PCB1-RXD0{slash}GPIO15-Pad10)") (class "Default")
      (node (ref "PCB1") (pin "10") (pinfunction "RXD0/GPIO15_10") (pintype "bidirectional"))
    )
    (net (code "90") (name "unconnected-(PCB1-TL-PadPE_TL)") (class "Default")
      (node (ref "PCB1") (pin "PE_TL") (pinfunction "TL_PE_TL") (pintype "bidirectional"))
    )
    (net (code "91") (name "unconnected-(PCB1-TR-PadPE_TR)") (class "Default")
      (node (ref "PCB1") (pin "PE_TR") (pinfunction "TR_PE_TR") (pintype "bidirectional"))
    )
    (net (code "92") (name "unconnected-(PCB1-TXD0{slash}GPIO14-Pad8)") (class "Default")
      (node (ref "PCB1") (pin "8") (pinfunction "TXD0/GPIO14_8") (pintype "bidirectional"))
    )
    (net (code "93") (name "unconnected-(PCB1-~{CE}{slash}GPIO07-Pad26)") (class "Default")
      (node (ref "PCB1") (pin "26") (pinfunction "~{CE}/GPIO07_26") (pintype "bidirectional"))
    )
  )
)
